# LED_Matrix.net
KiCad netlist of a schematic drawn in Altium Designer
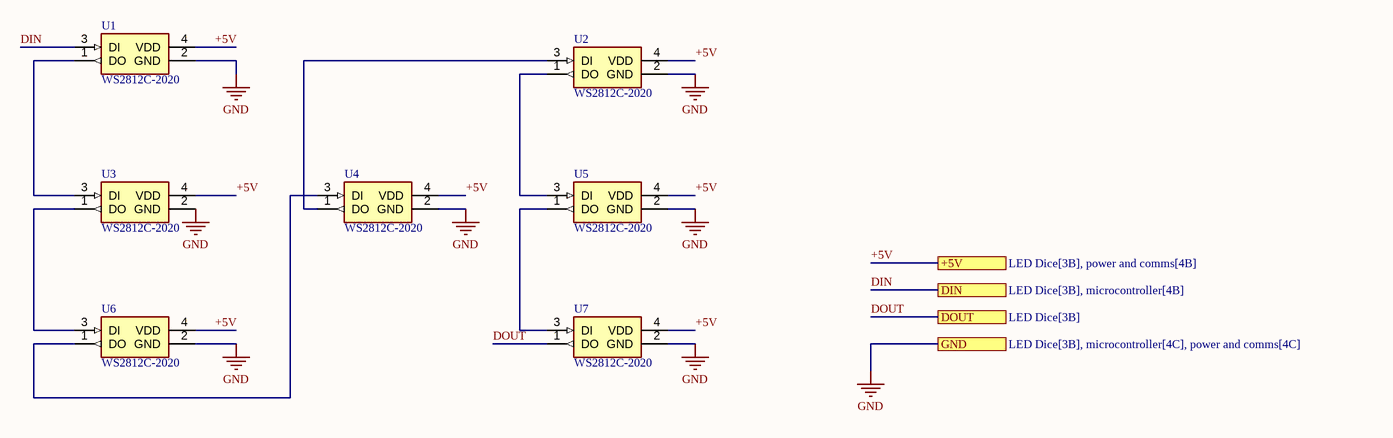
[diagram p0: LED Matrix.SchDoc]

(export (version "E")
  (design (tool "Eeschema 10.0.6"))
  (components
    (comp (ref "U1")
      (value "WS2812C-2020")
      (footprint "LED_WS2812C-2020")
      (description "Intelligent control LED integrated light source")
      (fields (field (name "MF") "Worldsemi"))
      (libsource (lib "WS2812C-2020") (part "WS2812C-2020"))
    )
    (comp (ref "U2")
      (value "WS2812C-2020")
      (footprint "LED_WS2812C-2020")
      (description "Intelligent control LED integrated light source")
      (fields (field (name "MF") "Worldsemi"))
      (libsource (lib "WS2812C-2020") (part "WS2812C-2020"))
    )
    (comp (ref "U3")
      (value "WS2812C-2020")
      (footprint "LED_WS2812C-2020")
      (description "Intelligent control LED integrated light source")
      (fields (field (name "MF") "Worldsemi"))
      (libsource (lib "WS2812C-2020") (part "WS2812C-2020"))
    )
    (comp (ref "U4")
      (value "WS2812C-2020")
      (footprint "LED_WS2812C-2020")
      (description "Intelligent control LED integrated light source")
      (fields (field (name "MF") "Worldsemi"))
      (libsource (lib "WS2812C-2020") (part "WS2812C-2020"))
    )
    (comp (ref "U5")
      (value "WS2812C-2020")
      (footprint "LED_WS2812C-2020")
      (description "Intelligent control LED integrated light source")
      (fields (field (name "MF") "Worldsemi"))
      (libsource (lib "WS2812C-2020") (part "WS2812C-2020"))
    )
    (comp (ref "U6")
      (value "WS2812C-2020")
      (footprint "LED_WS2812C-2020")
      (description "Intelligent control LED integrated light source")
      (fields (field (name "MF") "Worldsemi"))
      (libsource (lib "WS2812C-2020") (part "WS2812C-2020"))
    )
    (comp (ref "U7")
      (value "WS2812C-2020")
      (footprint "LED_WS2812C-2020")
      (description "Intelligent control LED integrated light source")
      (fields (field (name "MF") "Worldsemi"))
      (libsource (lib "WS2812C-2020") (part "WS2812C-2020"))
    )
  )
  (nets
    (net (code "1") (name "/+5V") (class "Default")
      (node (ref "U1") (pin "4") (pinfunction "VDD_4") (pintype "power_in"))
      (node (ref "U2") (pin "4") (pinfunction "VDD_4") (pintype "power_in"))
      (node (ref "U3") (pin "4") (pinfunction "VDD_4") (pintype "power_in"))
      (node (ref "U4") (pin "4") (pinfunction "VDD_4") (pintype "power_in"))
      (node (ref "U5") (pin "4") (pinfunction "VDD_4") (pintype "power_in"))
      (node (ref "U6") (pin "4") (pinfunction "VDD_4") (pintype "power_in"))
      (node (ref "U7") (pin "4") (pinfunction "VDD_4") (pintype "power_in"))
    )
    (net (code "2") (name "/DIN") (class "Default")
      (node (ref "U1") (pin "3") (pinfunction "DI_3") (pintype "input"))
    )
    (net (code "3") (name "/DOUT") (class "Default")
      (node (ref "U7") (pin "1") (pinfunction "DO_1") (pintype "output"))
    )
    (net (code "4") (name "GND") (class "Default")
      (node (ref "U1") (pin "2") (pinfunction "GND_2") (pintype "power_in"))
      (node (ref "U2") (pin "2") (pinfunction "GND_2") (pintype "power_in"))
      (node (ref "U3") (pin "2") (pinfunction "GND_2") (pintype "power_in"))
      (node (ref "U4") (pin "2") (pinfunction "GND_2") (pintype "power_in"))
      (node (ref "U5") (pin "2") (pinfunction "GND_2") (pintype "power_in"))
      (node (ref "U6") (pin "2") (pinfunction "GND_2") (pintype "power_in"))
      (node (ref "U7") (pin "2") (pinfunction "GND_2") (pintype "power_in"))
    )
    (net (code "5") (name "Net-(U1-DO)") (class "Default")
      (node (ref "U1") (pin "1") (pinfunction "DO_1") (pintype "output"))
      (node (ref "U3") (pin "3") (pinfunction "DI_3") (pintype "input"))
    )
    (net (code "6") (name "Net-(U2-DI)") (class "Default")
      (node (ref "U2") (pin "3") (pinfunction "DI_3") (pintype "input"))
      (node (ref "U4") (pin "1") (pinfunction "DO_1") (pintype "output"))
    )
    (net (code "7") (name "Net-(U2-DO)") (class "Default")
      (node (ref "U2") (pin "1") (pinfunction "DO_1") (pintype "output"))
      (node (ref "U5") (pin "3") (pinfunction "DI_3") (pintype "input"))
    )
    (net (code "8") (name "Net-(U3-DO)") (class "Default")
      (node (ref "U3") (pin "1") (pinfunction "DO_1") (pintype "output"))
      (node (ref "U6") (pin "3") (pinfunction "DI_3") (pintype "input"))
    )
    (net (code "9") (name "Net-(U4-DI)") (class "Default")
      (node (ref "U4") (pin "3") (pinfunction "DI_3") (pintype "input"))
      (node (ref "U6") (pin "1") (pinfunction "DO_1") (pintype "output"))
    )
    (net (code "10") (name "Net-(U5-DO)") (class "Default")
      (node (ref "U5") (pin "1") (pinfunction "DO_1") (pintype "output"))
      (node (ref "U7") (pin "3") (pinfunction "DI_3") (pintype "input"))
    )
  )
)
